# Power.net
KiCad netlist of a schematic drawn in Altium Designer
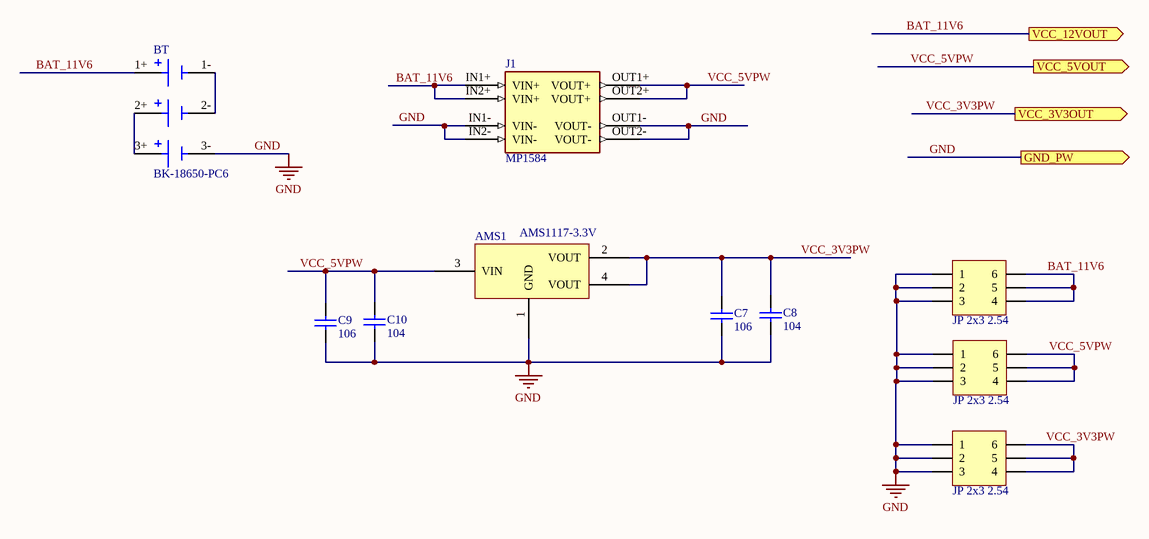
[diagram p0: Power.SchDoc]

(export (version "E")
  (design (tool "Eeschema 10.0.6"))
  (components
    (comp (ref "AMS1")
      (value "AMS1117-3.3V")
      (footprint "SOT223")
      (description "Dán")
      (libsource (lib "Altium_Lib_by_KhueNguyenCreator") (part "AMS1117 SMD"))
    )
    (comp (ref "BT")
      (value "BK-18650-PC6")
      (footprint "BAT_BK-18650-PC6")
      (description "Battery Holder _Open_ 18650 3 Cell PC Pin")
      (fields (field (name "MF") "MPD"))
      (libsource (lib "BK-18650-PC6") (part "BK-18650-PC6"))
    )
    (comp (ref "C7")
      (value "106")
      (footprint "tu 0805")
      (description "Dán")
      (libsource (lib "Altium_Lib_by_KhueNguyenCreator") (part "Tu 0805 106 16V 10%"))
    )
    (comp (ref "C8")
      (value "104")
      (footprint "tu 0805")
      (description "Dán")
      (libsource (lib "Altium_Lib_by_KhueNguyenCreator") (part "Tu 0805 104 50V 10%"))
    )
    (comp (ref "C9")
      (value "106")
      (footprint "tu 0805")
      (description "Dán")
      (libsource (lib "Altium_Lib_by_KhueNguyenCreator") (part "Tu 0805 106 16V 10%"))
    )
    (comp (ref "C10")
      (value "104")
      (footprint "tu 0805")
      (description "Dán")
      (libsource (lib "Altium_Lib_by_KhueNguyenCreator") (part "Tu 0805 104 50V 10%"))
    )
    (comp (ref "J1")
      (value "MP1584")
      (footprint "DC-BRICK")
      (fields (field (name "MF") "Monolithic Power"))
      (libsource (lib "MP1584") (part "MP1584"))
    )
    (comp (ref "JP1")
      (value "JP 2x3 2.54")
      (footprint "JP 2x3 DT")
      (description "Cắm")
      (libsource (lib "Altium_Lib_by_KhueNguyenCreator") (part "JP 2x3 2.54 Duc Thang"))
    )
    (comp (ref "JP2")
      (value "JP 2x3 2.54")
      (footprint "JP 2x3 DT")
      (description "Cắm")
      (libsource (lib "Altium_Lib_by_KhueNguyenCreator") (part "JP 2x3 2.54 Duc Thang"))
    )
    (comp (ref "JP3")
      (value "JP 2x3 2.54")
      (footprint "JP 2x3 DT")
      (description "Cắm")
      (libsource (lib "Altium_Lib_by_KhueNguyenCreator") (part "JP 2x3 2.54 Duc Thang"))
    )
  )
  (nets
    (net (code "1") (name "/BAT_11V6") (class "Default")
      (node (ref "BT") (pin "1+") (pinfunction "1+_1+") (pintype "passive"))
      (node (ref "J1") (pin "IN1+") (pinfunction "VIN+_IN1+") (pintype "input"))
      (node (ref "J1") (pin "IN2+") (pinfunction "VIN+_IN2+") (pintype "input"))
      (node (ref "JP1") (pin "4") (pinfunction "4_4") (pintype "passive"))
      (node (ref "JP1") (pin "5") (pinfunction "5_5") (pintype "passive"))
      (node (ref "JP1") (pin "6") (pinfunction "6_6") (pintype "passive"))
    )
    (net (code "2") (name "/VCC_3V3PW") (class "Default")
      (node (ref "AMS1") (pin "2") (pinfunction "VOUT_2") (pintype "passive"))
      (node (ref "AMS1") (pin "4") (pinfunction "VOUT_4") (pintype "passive"))
      (node (ref "C7") (pin "1") (pinfunction "1_1") (pintype "passive"))
      (node (ref "C8") (pin "1") (pinfunction "1_1") (pintype "passive"))
      (node (ref "JP3") (pin "4") (pinfunction "4_4") (pintype "passive"))
      (node (ref "JP3") (pin "5") (pinfunction "5_5") (pintype "passive"))
      (node (ref "JP3") (pin "6") (pinfunction "6_6") (pintype "passive"))
    )
    (net (code "3") (name "/VCC_5VPW") (class "Default")
      (node (ref "AMS1") (pin "3") (pinfunction "VIN_3") (pintype "passive"))
      (node (ref "C10") (pin "1") (pinfunction "1_1") (pintype "passive"))
      (node (ref "C9") (pin "1") (pinfunction "1_1") (pintype "passive"))
      (node (ref "J1") (pin "OUT1+") (pinfunction "VOUT+_OUT1+") (pintype "output"))
      (node (ref "J1") (pin "OUT2+") (pinfunction "VOUT+_OUT2+") (pintype "output"))
      (node (ref "JP2") (pin "4") (pinfunction "4_4") (pintype "passive"))
      (node (ref "JP2") (pin "5") (pinfunction "5_5") (pintype "passive"))
      (node (ref "JP2") (pin "6") (pinfunction "6_6") (pintype "passive"))
    )
    (net (code "4") (name "GND") (class "Default")
      (node (ref "AMS1") (pin "1") (pinfunction "GND_1") (pintype "passive"))
      (node (ref "BT") (pin "3-") (pinfunction "3-_3-") (pintype "passive"))
      (node (ref "C10") (pin "2") (pinfunction "2_2") (pintype "passive"))
      (node (ref "C7") (pin "2") (pinfunction "2_2") (pintype "passive"))
      (node (ref "C8") (pin "2") (pinfunction "2_2") (pintype "passive"))
      (node (ref "C9") (pin "2") (pinfunction "2_2") (pintype "passive"))
      (node (ref "J1") (pin "IN1-") (pinfunction "VIN-_IN1-") (pintype "input"))
      (node (ref "J1") (pin "IN2-") (pinfunction "VIN-_IN2-") (pintype "input"))
      (node (ref "J1") (pin "OUT1-") (pinfunction "VOUT-_OUT1-") (pintype "output"))
      (node (ref "J1") (pin "OUT2-") (pinfunction "VOUT-_OUT2-") (pintype "output"))
      (node (ref "JP1") (pin "1") (pinfunction "1_1") (pintype "passive"))
      (node (ref "JP1") (pin "2") (pinfunction "2_2") (pintype "passive"))
      (node (ref "JP1") (pin "3") (pinfunction "3_3") (pintype "passive"))
      (node (ref "JP2") (pin "1") (pinfunction "1_1") (pintype "passive"))
      (node (ref "JP2") (pin "2") (pinfunction "2_2") (pintype "passive"))
      (node (ref "JP2") (pin "3") (pinfunction "3_3") (pintype "passive"))
      (node (ref "JP3") (pin "1") (pinfunction "1_1") (pintype "passive"))
      (node (ref "JP3") (pin "2") (pinfunction "2_2") (pintype "passive"))
      (node (ref "JP3") (pin "3") (pinfunction "3_3") (pintype "passive"))
    )
    (net (code "5") (name "Net-(BT-Pad1-)") (class "Default")
      (node (ref "BT") (pin "1-") (pinfunction "1-_1-") (pintype "passive"))
      (node (ref "BT") (pin "2-") (pinfunction "2-_2-") (pintype "passive"))
    )
    (net (code "6") (name "Net-(BT-Pad2+)") (class "Default")
      (node (ref "BT") (pin "2+") (pinfunction "2+_2+") (pintype "passive"))
      (node (ref "BT") (pin "3+") (pinfunction "3+_3+") (pintype "passive"))
    )
  )
)
